# Layout_Design_File.net
KiCad netlist of a schematic drawn in EAGLE
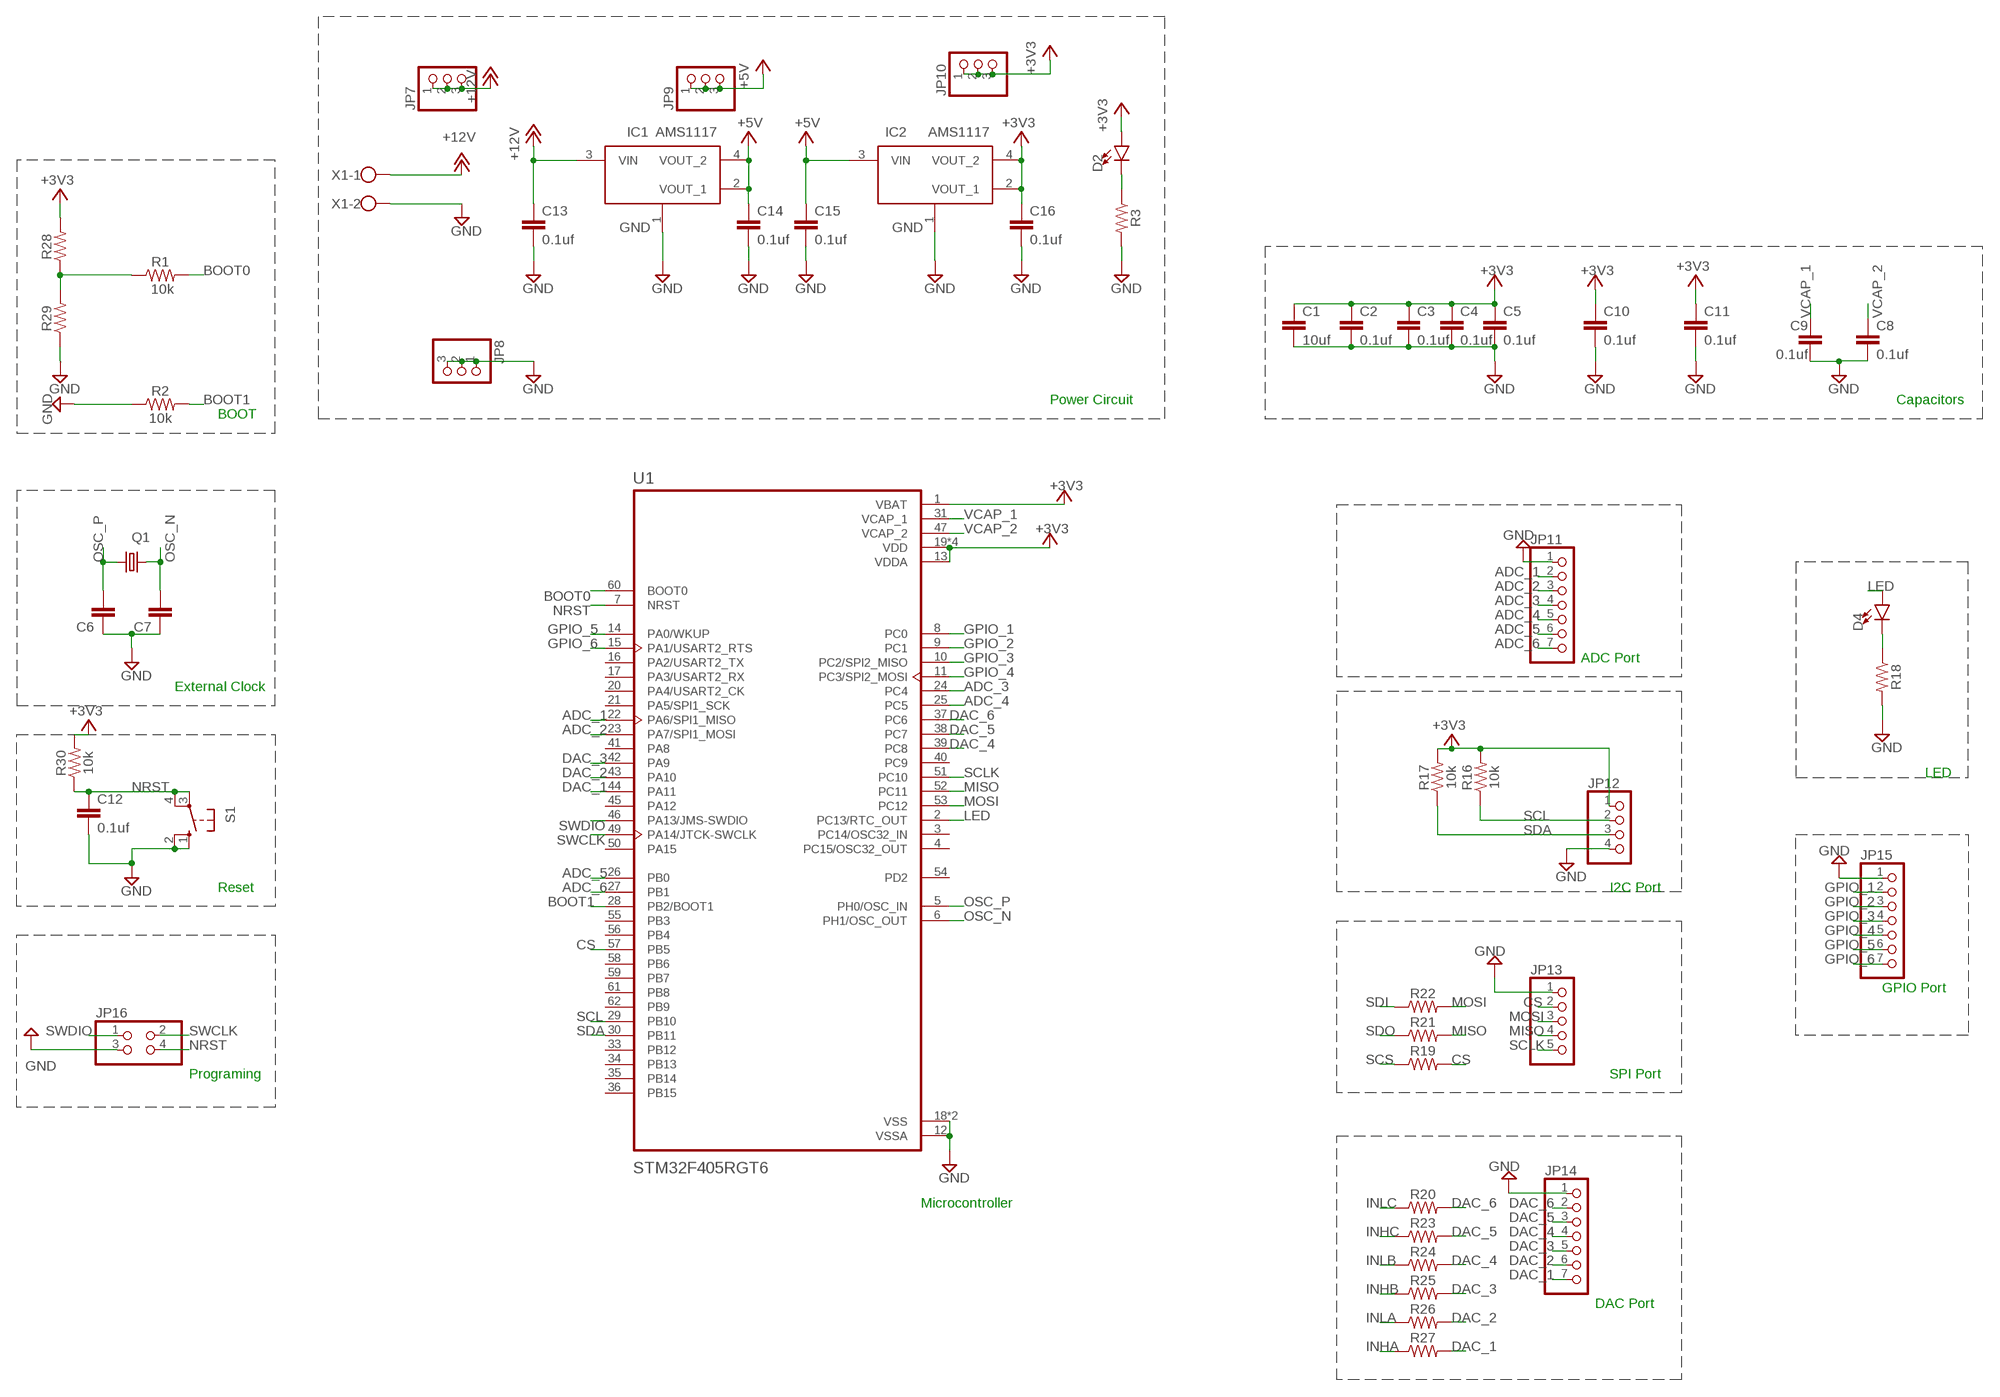
[diagram p0: schematic, sheet 1]
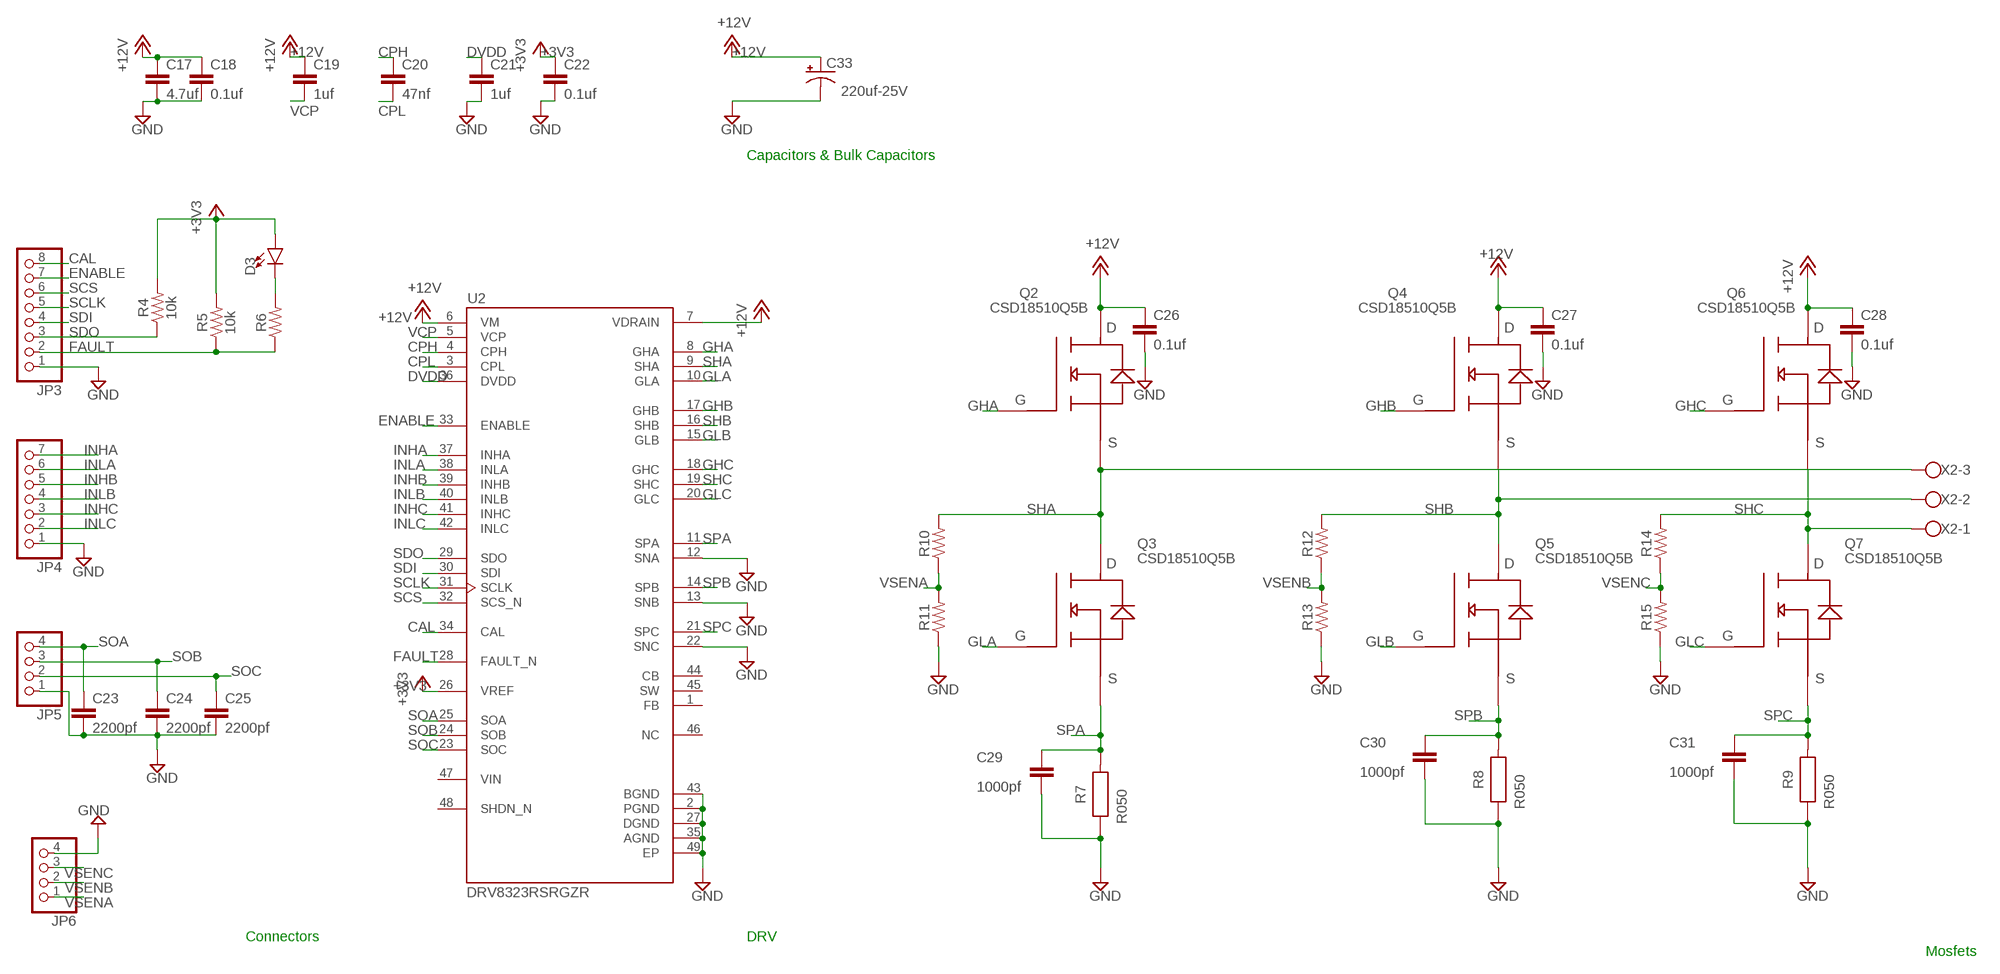
[diagram p1: schematic, sheet 2]

(export (version "E")
  (design (tool "Eeschema 10.0.6"))
  (components
    (comp (ref "C1")
      (value "10uf")
      (footprint "eagle-import:0603")
      (libsource (lib "eagle-import") (part "CAP-0603"))
    )
    (comp (ref "C2")
      (value "0.1uf")
      (footprint "eagle-import:0603")
      (libsource (lib "eagle-import") (part "CAP-0603"))
    )
    (comp (ref "C3")
      (value "0.1uf")
      (footprint "eagle-import:0603")
      (libsource (lib "eagle-import") (part "CAP-0603"))
    )
    (comp (ref "C4")
      (value "0.1uf")
      (footprint "eagle-import:0603")
      (libsource (lib "eagle-import") (part "CAP-0603"))
    )
    (comp (ref "C5")
      (value "0.1uf")
      (footprint "eagle-import:0603")
      (libsource (lib "eagle-import") (part "CAP-0603"))
    )
    (comp (ref "C6")
      (value "CAP-0603")
      (footprint "eagle-import:0603")
      (libsource (lib "eagle-import") (part "CAP-0603"))
    )
    (comp (ref "C7")
      (value "CAP-0603")
      (footprint "eagle-import:0603")
      (libsource (lib "eagle-import") (part "CAP-0603"))
    )
    (comp (ref "C8")
      (value "0.1uf")
      (footprint "eagle-import:0603")
      (libsource (lib "eagle-import") (part "CAP-0603"))
    )
    (comp (ref "C9")
      (value "0.1uf")
      (footprint "eagle-import:0603")
      (libsource (lib "eagle-import") (part "CAP-0603"))
    )
    (comp (ref "C10")
      (value "0.1uf")
      (footprint "eagle-import:0603")
      (libsource (lib "eagle-import") (part "CAP-0603"))
    )
    (comp (ref "C11")
      (value "0.1uf")
      (footprint "eagle-import:0603")
      (libsource (lib "eagle-import") (part "CAP-0603"))
    )
    (comp (ref "C12")
      (value "0.1uf")
      (footprint "eagle-import:0603")
      (libsource (lib "eagle-import") (part "CAP-0603"))
    )
    (comp (ref "C13")
      (value "0.1uf")
      (footprint "eagle-import:0603")
      (libsource (lib "eagle-import") (part "CAP-0603"))
    )
    (comp (ref "C14")
      (value "0.1uf")
      (footprint "eagle-import:0603")
      (libsource (lib "eagle-import") (part "CAP-0603"))
    )
    (comp (ref "C15")
      (value "0.1uf")
      (footprint "eagle-import:0603")
      (libsource (lib "eagle-import") (part "CAP-0603"))
    )
    (comp (ref "C16")
      (value "0.1uf")
      (footprint "eagle-import:0603")
      (libsource (lib "eagle-import") (part "CAP-0603"))
    )
    (comp (ref "D2")
      (value "LED1206")
      (footprint "eagle-import:LED-1206")
      (libsource (lib "eagle-import") (part "LED1206"))
    )
    (comp (ref "D4")
      (value "LED1206")
      (footprint "eagle-import:LED-1206")
      (libsource (lib "eagle-import") (part "LED1206"))
    )
    (comp (ref "IC1")
      (value "AMS1117")
      (footprint "eagle-import:SOT229P700X180-4N")
      (libsource (lib "eagle-import") (part "AMS1117"))
    )
    (comp (ref "IC2")
      (value "AMS1117")
      (footprint "eagle-import:SOT229P700X180-4N")
      (libsource (lib "eagle-import") (part "AMS1117"))
    )
    (comp (ref "JP7")
      (value "PINHD-1X3")
      (footprint "eagle-import:1X03")
      (libsource (lib "eagle-import") (part "PINHD-1X3"))
    )
    (comp (ref "JP8")
      (value "PINHD-1X3")
      (footprint "eagle-import:1X03")
      (libsource (lib "eagle-import") (part "PINHD-1X3"))
    )
    (comp (ref "JP9")
      (value "PINHD-1X3")
      (footprint "eagle-import:1X03")
      (libsource (lib "eagle-import") (part "PINHD-1X3"))
    )
    (comp (ref "JP10")
      (value "PINHD-1X3")
      (footprint "eagle-import:1X03")
      (libsource (lib "eagle-import") (part "PINHD-1X3"))
    )
    (comp (ref "JP11")
      (value "PINHD-1X7")
      (footprint "eagle-import:1X07")
      (libsource (lib "eagle-import") (part "PINHD-1X7"))
    )
    (comp (ref "JP12")
      (value "PINHD-1X4")
      (footprint "eagle-import:1X04")
      (libsource (lib "eagle-import") (part "PINHD-1X4"))
    )
    (comp (ref "JP13")
      (value "PINHD-1X5")
      (footprint "eagle-import:1X05")
      (libsource (lib "eagle-import") (part "PINHD-1X5"))
    )
    (comp (ref "JP14")
      (value "PINHD-1X7")
      (footprint "eagle-import:1X07")
      (libsource (lib "eagle-import") (part "PINHD-1X7"))
    )
    (comp (ref "JP15")
      (value "PINHD-1X7")
      (footprint "eagle-import:1X07")
      (libsource (lib "eagle-import") (part "PINHD-1X7"))
    )
    (comp (ref "JP16")
      (value "PINHD-2X2")
      (footprint "eagle-import:2X02")
      (libsource (lib "eagle-import") (part "PINHD-2X2"))
    )
    (comp (ref "Q1")
      (value "CRYSTALHC49S")
      (footprint "eagle-import:HC49_S")
      (libsource (lib "eagle-import") (part "CRYSTALHC49S"))
    )
    (comp (ref "R1")
      (value "10k")
      (footprint "eagle-import:0603")
      (libsource (lib "eagle-import") (part "RESISTOR0603"))
    )
    (comp (ref "R2")
      (value "10k")
      (footprint "eagle-import:0603")
      (libsource (lib "eagle-import") (part "RESISTOR0603"))
    )
    (comp (ref "R3")
      (value "RESISTOR0603")
      (footprint "eagle-import:0603")
      (libsource (lib "eagle-import") (part "RESISTOR0603"))
    )
    (comp (ref "R16")
      (value "10k")
      (footprint "eagle-import:0603")
      (libsource (lib "eagle-import") (part "RESISTOR0603"))
    )
    (comp (ref "R17")
      (value "10k")
      (footprint "eagle-import:0603")
      (libsource (lib "eagle-import") (part "RESISTOR0603"))
    )
    (comp (ref "R18")
      (value "RESISTOR0603")
      (footprint "eagle-import:0603")
      (libsource (lib "eagle-import") (part "RESISTOR0603"))
    )
    (comp (ref "R19")
      (value "RESISTOR0603")
      (footprint "eagle-import:0603")
      (libsource (lib "eagle-import") (part "RESISTOR0603"))
    )
    (comp (ref "R20")
      (value "RESISTOR0603")
      (footprint "eagle-import:0603")
      (libsource (lib "eagle-import") (part "RESISTOR0603"))
    )
    (comp (ref "R21")
      (value "RESISTOR0603")
      (footprint "eagle-import:0603")
      (libsource (lib "eagle-import") (part "RESISTOR0603"))
    )
    (comp (ref "R22")
      (value "RESISTOR0603")
      (footprint "eagle-import:0603")
      (libsource (lib "eagle-import") (part "RESISTOR0603"))
    )
    (comp (ref "R23")
      (value "RESISTOR0603")
      (footprint "eagle-import:0603")
      (libsource (lib "eagle-import") (part "RESISTOR0603"))
    )
    (comp (ref "R24")
      (value "RESISTOR0603")
      (footprint "eagle-import:0603")
      (libsource (lib "eagle-import") (part "RESISTOR0603"))
    )
    (comp (ref "R25")
      (value "RESISTOR0603")
      (footprint "eagle-import:0603")
      (libsource (lib "eagle-import") (part "RESISTOR0603"))
    )
    (comp (ref "R26")
      (value "RESISTOR0603")
      (footprint "eagle-import:0603")
      (libsource (lib "eagle-import") (part "RESISTOR0603"))
    )
    (comp (ref "R27")
      (value "RESISTOR0603")
      (footprint "eagle-import:0603")
      (libsource (lib "eagle-import") (part "RESISTOR0603"))
    )
    (comp (ref "R28")
      (value "RESISTOR0603")
      (footprint "eagle-import:0603")
      (libsource (lib "eagle-import") (part "RESISTOR0603"))
    )
    (comp (ref "R29")
      (value "RESISTOR0603")
      (footprint "eagle-import:0603")
      (libsource (lib "eagle-import") (part "RESISTOR0603"))
    )
    (comp (ref "R30")
      (value "10k")
      (footprint "eagle-import:0603")
      (libsource (lib "eagle-import") (part "RESISTOR0603"))
    )
    (comp (ref "S1")
      (value "10-XX")
      (footprint "eagle-import:B3F-10XX")
      (fields (field (name "MPN") "B3F-1000"))
      (libsource (lib "eagle-import") (part "10-XX"))
    )
    (comp (ref "U1")
      (value "STM32F405RGT6")
      (footprint "eagle-import:QFP50P1200X1200X160-64N")
      (fields (field (name "MF") "STMicroelectronics"))
      (libsource (lib "eagle-import") (part "STM32F405RGT6"))
    )
    (comp (ref "X1")
      (value "W237-102")
      (footprint "eagle-import:W237-102")
      (fields (field (name "MPN") "237-102"))
      (libsource (lib "eagle-import") (part "W237-102"))
    )
    (comp (ref "C17")
      (value "4.7uf")
      (footprint "eagle-import:0603")
      (libsource (lib "eagle-import") (part "CAP-0603"))
    )
    (comp (ref "C18")
      (value "0.1uf")
      (footprint "eagle-import:0603")
      (libsource (lib "eagle-import") (part "CAP-0603"))
    )
    (comp (ref "C19")
      (value "1uf")
      (footprint "eagle-import:0603")
      (libsource (lib "eagle-import") (part "CAP-0603"))
    )
    (comp (ref "C20")
      (value "47nf")
      (footprint "eagle-import:0603")
      (libsource (lib "eagle-import") (part "CAP-0603"))
    )
    (comp (ref "C21")
      (value "1uf")
      (footprint "eagle-import:0603")
      (libsource (lib "eagle-import") (part "CAP-0603"))
    )
    (comp (ref "C22")
      (value "0.1uf")
      (footprint "eagle-import:0603")
      (libsource (lib "eagle-import") (part "CAP-0603"))
    )
    (comp (ref "C23")
      (value "2200pf")
      (footprint "eagle-import:0603")
      (libsource (lib "eagle-import") (part "CAP-0603"))
    )
    (comp (ref "C24")
      (value "2200pf")
      (footprint "eagle-import:0603")
      (libsource (lib "eagle-import") (part "CAP-0603"))
    )
    (comp (ref "C25")
      (value "2200pf")
      (footprint "eagle-import:0603")
      (libsource (lib "eagle-import") (part "CAP-0603"))
    )
    (comp (ref "C26")
      (value "0.1uf")
      (footprint "eagle-import:0603")
      (libsource (lib "eagle-import") (part "CAP-0603"))
    )
    (comp (ref "C27")
      (value "0.1uf")
      (footprint "eagle-import:0603")
      (libsource (lib "eagle-import") (part "CAP-0603"))
    )
    (comp (ref "C28")
      (value "0.1uf")
      (footprint "eagle-import:0603")
      (libsource (lib "eagle-import") (part "CAP-0603"))
    )
    (comp (ref "C29")
      (value "1000pf")
      (footprint "eagle-import:0603")
      (libsource (lib "eagle-import") (part "CAP-0603"))
    )
    (comp (ref "C30")
      (value "1000pf")
      (footprint "eagle-import:0603")
      (libsource (lib "eagle-import") (part "CAP-0603"))
    )
    (comp (ref "C31")
      (value "1000pf")
      (footprint "eagle-import:0603")
      (libsource (lib "eagle-import") (part "CAP-0603"))
    )
    (comp (ref "C33")
      (value "220uf-25V")
      (footprint "eagle-import:CPOL-RADIAL-5MM-10MM-NS")
      (libsource (lib "eagle-import") (part "1000UF-RADIAL-5MM-25V-20%-NO-SILK"))
    )
    (comp (ref "D3")
      (value "LED1206")
      (footprint "eagle-import:LED-1206")
      (libsource (lib "eagle-import") (part "LED1206"))
    )
    (comp (ref "JP3")
      (value "PINHD-1X8")
      (footprint "eagle-import:1X08")
      (libsource (lib "eagle-import") (part "PINHD-1X8"))
    )
    (comp (ref "JP4")
      (value "PINHD-1X7")
      (footprint "eagle-import:1X07")
      (libsource (lib "eagle-import") (part "PINHD-1X7"))
    )
    (comp (ref "JP5")
      (value "PINHD-1X4")
      (footprint "eagle-import:1X04")
      (libsource (lib "eagle-import") (part "PINHD-1X4"))
    )
    (comp (ref "JP6")
      (value "PINHD-1X4")
      (footprint "eagle-import:1X04")
      (libsource (lib "eagle-import") (part "PINHD-1X4"))
    )
    (comp (ref "Q2")
      (value "CSD18510Q5B")
      (footprint "eagle-import:CSD18540Q5BT")
      (fields (field (name "MOUSER_PART_NUMBER") "595-CSD18510Q5B"))
      (libsource (lib "eagle-import") (part "CSD18510Q5B"))
    )
    (comp (ref "Q3")
      (value "CSD18510Q5B")
      (footprint "eagle-import:CSD18540Q5BT")
      (fields (field (name "MOUSER_PART_NUMBER") "595-CSD18510Q5B"))
      (libsource (lib "eagle-import") (part "CSD18510Q5B"))
    )
    (comp (ref "Q4")
      (value "CSD18510Q5B")
      (footprint "eagle-import:CSD18540Q5BT")
      (fields (field (name "MOUSER_PART_NUMBER") "595-CSD18510Q5B"))
      (libsource (lib "eagle-import") (part "CSD18510Q5B"))
    )
    (comp (ref "Q5")
      (value "CSD18510Q5B")
      (footprint "eagle-import:CSD18540Q5BT")
      (fields (field (name "MOUSER_PART_NUMBER") "595-CSD18510Q5B"))
      (libsource (lib "eagle-import") (part "CSD18510Q5B"))
    )
    (comp (ref "Q6")
      (value "CSD18510Q5B")
      (footprint "eagle-import:CSD18540Q5BT")
      (fields (field (name "MOUSER_PART_NUMBER") "595-CSD18510Q5B"))
      (libsource (lib "eagle-import") (part "CSD18510Q5B"))
    )
    (comp (ref "Q7")
      (value "CSD18510Q5B")
      (footprint "eagle-import:CSD18540Q5BT")
      (fields (field (name "MOUSER_PART_NUMBER") "595-CSD18510Q5B"))
      (libsource (lib "eagle-import") (part "CSD18510Q5B"))
    )
    (comp (ref "R4")
      (value "10k")
      (footprint "eagle-import:0603")
      (libsource (lib "eagle-import") (part "RESISTOR0603"))
    )
    (comp (ref "R5")
      (value "10k")
      (footprint "eagle-import:0603")
      (libsource (lib "eagle-import") (part "RESISTOR0603"))
    )
    (comp (ref "R6")
      (value "RESISTOR0603")
      (footprint "eagle-import:0603")
      (libsource (lib "eagle-import") (part "RESISTOR0603"))
    )
    (comp (ref "R7")
      (value "R050")
      (footprint "eagle-import:WRIS_PSMC_2512_6.3X3.1X0.58X2.2(LXWXHXPW)")
      (libsource (lib "eagle-import") (part "WRIS-PSMC_2512_6.3X3.1X0.58X2.2_580070763001"))
    )
    (comp (ref "R8")
      (value "R050")
      (footprint "eagle-import:WRIS_PSMC_2512_6.3X3.1X0.58X2.2(LXWXHXPW)")
      (libsource (lib "eagle-import") (part "WRIS-PSMC_2512_6.3X3.1X0.58X2.2_580070763001"))
    )
    (comp (ref "R9")
      (value "R050")
      (footprint "eagle-import:WRIS_PSMC_2512_6.3X3.1X0.58X2.2(LXWXHXPW)")
      (libsource (lib "eagle-import") (part "WRIS-PSMC_2512_6.3X3.1X0.58X2.2_580070763001"))
    )
    (comp (ref "R10")
      (value "RESISTOR0603")
      (footprint "eagle-import:0603")
      (libsource (lib "eagle-import") (part "RESISTOR0603"))
    )
    (comp (ref "R11")
      (value "RESISTOR0603")
      (footprint "eagle-import:0603")
      (libsource (lib "eagle-import") (part "RESISTOR0603"))
    )
    (comp (ref "R12")
      (value "RESISTOR0603")
      (footprint "eagle-import:0603")
      (libsource (lib "eagle-import") (part "RESISTOR0603"))
    )
    (comp (ref "R13")
      (value "RESISTOR0603")
      (footprint "eagle-import:0603")
      (libsource (lib "eagle-import") (part "RESISTOR0603"))
    )
    (comp (ref "R14")
      (value "RESISTOR0603")
      (footprint "eagle-import:0603")
      (libsource (lib "eagle-import") (part "RESISTOR0603"))
    )
    (comp (ref "R15")
      (value "RESISTOR0603")
      (footprint "eagle-import:0603")
      (libsource (lib "eagle-import") (part "RESISTOR0603"))
    )
    (comp (ref "U2")
      (value "DRV8323RSRGZR")
      (footprint "eagle-import:QFN50P700X700X100-49N")
      (fields (field (name "MF") "Texas Instruments"))
      (libsource (lib "eagle-import") (part "DRV8323RSRGZR"))
    )
    (comp (ref "X2")
      (value "W237-103")
      (footprint "eagle-import:W237-103")
      (fields (field (name "MPN") "237-103"))
      (libsource (lib "eagle-import") (part "W237-103"))
    )
  )
  (nets
    (net (code "1") (name "+3V3") (class "Default")
      (node (ref "C1") (pin "1") (pinfunction "1_1") (pintype "passive"))
      (node (ref "C10") (pin "1") (pinfunction "1_1") (pintype "passive"))
      (node (ref "C11") (pin "1") (pinfunction "1_1") (pintype "passive"))
      (node (ref "C16") (pin "1") (pinfunction "1_1") (pintype "passive"))
      (node (ref "C2") (pin "1") (pinfunction "1_1") (pintype "passive"))
      (node (ref "C22") (pin "1") (pinfunction "1_1") (pintype "passive"))
      (node (ref "C3") (pin "1") (pinfunction "1_1") (pintype "passive"))
      (node (ref "C4") (pin "1") (pinfunction "1_1") (pintype "passive"))
      (node (ref "C5") (pin "1") (pinfunction "1_1") (pintype "passive"))
      (node (ref "D2") (pin "A") (pinfunction "A_A") (pintype "passive"))
      (node (ref "D3") (pin "A") (pinfunction "A_A") (pintype "passive"))
      (node (ref "IC2") (pin "2") (pinfunction "VOUT_1_2") (pintype "bidirectional"))
      (node (ref "IC2") (pin "4") (pinfunction "VOUT_2_4") (pintype "bidirectional"))
      (node (ref "JP10") (pin "1") (pinfunction "1_1") (pintype "passive"))
      (node (ref "JP10") (pin "2") (pinfunction "2_2") (pintype "passive"))
      (node (ref "JP10") (pin "3") (pinfunction "3_3") (pintype "passive"))
      (node (ref "JP12") (pin "1") (pinfunction "1_1") (pintype "passive"))
      (node (ref "R16") (pin "2") (pinfunction "2_2") (pintype "passive"))
      (node (ref "R17") (pin "2") (pinfunction "2_2") (pintype "passive"))
      (node (ref "R28") (pin "2") (pinfunction "2_2") (pintype "passive"))
      (node (ref "R30") (pin "2") (pinfunction "2_2") (pintype "passive"))
      (node (ref "R4") (pin "2") (pinfunction "2_2") (pintype "passive"))
      (node (ref "R5") (pin "2") (pinfunction "2_2") (pintype "passive"))
      (node (ref "U1") (pin "1") (pinfunction "VBAT_1") (pintype "power_in"))
      (node (ref "U1") (pin "13") (pinfunction "VDDA_13") (pintype "power_in"))
      (node (ref "U1") (pin "19") (pinfunction "VDD_19") (pintype "power_in"))
      (node (ref "U1") (pin "32") (pinfunction "VDD_32") (pintype "power_in"))
      (node (ref "U1") (pin "48") (pinfunction "VDD_48") (pintype "power_in"))
      (node (ref "U1") (pin "64") (pinfunction "VDD_64") (pintype "power_in"))
      (node (ref "U2") (pin "26") (pinfunction "VREF_26") (pintype "power_in"))
    )
    (net (code "2") (name "+5V") (class "Default")
      (node (ref "C14") (pin "1") (pinfunction "1_1") (pintype "passive"))
      (node (ref "C15") (pin "1") (pinfunction "1_1") (pintype "passive"))
      (node (ref "IC1") (pin "2") (pinfunction "VOUT_1_2") (pintype "bidirectional"))
      (node (ref "IC1") (pin "4") (pinfunction "VOUT_2_4") (pintype "bidirectional"))
      (node (ref "IC2") (pin "3") (pinfunction "VIN_3") (pintype "bidirectional"))
      (node (ref "JP9") (pin "1") (pinfunction "1_1") (pintype "passive"))
      (node (ref "JP9") (pin "2") (pinfunction "2_2") (pintype "passive"))
      (node (ref "JP9") (pin "3") (pinfunction "3_3") (pintype "passive"))
    )
    (net (code "3") (name "+12V") (class "Default")
      (node (ref "C13") (pin "1") (pinfunction "1_1") (pintype "passive"))
      (node (ref "C17") (pin "1") (pinfunction "1_1") (pintype "passive"))
      (node (ref "C18") (pin "1") (pinfunction "1_1") (pintype "passive"))
      (node (ref "C19") (pin "1") (pinfunction "1_1") (pintype "passive"))
      (node (ref "C26") (pin "1") (pinfunction "1_1") (pintype "passive"))
      (node (ref "C27") (pin "1") (pinfunction "1_1") (pintype "passive"))
      (node (ref "C28") (pin "1") (pinfunction "1_1") (pintype "passive"))
      (node (ref "C33") (pin "+") (pinfunction "+_+") (pintype "passive"))
      (node (ref "IC1") (pin "3") (pinfunction "VIN_3") (pintype "bidirectional"))
      (node (ref "JP7") (pin "1") (pinfunction "1_1") (pintype "passive"))
      (node (ref "JP7") (pin "2") (pinfunction "2_2") (pintype "passive"))
      (node (ref "JP7") (pin "3") (pinfunction "3_3") (pintype "passive"))
      (node (ref "Q2") (pin "5") (pinfunction "D_5") (pintype "bidirectional"))
      (node (ref "Q2") (pin "6") (pinfunction "D_6") (pintype "bidirectional"))
      (node (ref "Q2") (pin "7") (pinfunction "D_7") (pintype "bidirectional"))
      (node (ref "Q2") (pin "8") (pinfunction "D_8") (pintype "bidirectional"))
      (node (ref "Q2") (pin "9") (pinfunction "D_9") (pintype "bidirectional"))
      (node (ref "Q4") (pin "5") (pinfunction "D_5") (pintype "bidirectional"))
      (node (ref "Q4") (pin "6") (pinfunction "D_6") (pintype "bidirectional"))
      (node (ref "Q4") (pin "7") (pinfunction "D_7") (pintype "bidirectional"))
      (node (ref "Q4") (pin "8") (pinfunction "D_8") (pintype "bidirectional"))
      (node (ref "Q4") (pin "9") (pinfunction "D_9") (pintype "bidirectional"))
      (node (ref "Q6") (pin "5") (pinfunction "D_5") (pintype "bidirectional"))
      (node (ref "Q6") (pin "6") (pinfunction "D_6") (pintype "bidirectional"))
      (node (ref "Q6") (pin "7") (pinfunction "D_7") (pintype "bidirectional"))
      (node (ref "Q6") (pin "8") (pinfunction "D_8") (pintype "bidirectional"))
      (node (ref "Q6") (pin "9") (pinfunction "D_9") (pintype "bidirectional"))
      (node (ref "U2") (pin "6") (pinfunction "VM_6") (pintype "power_in"))
      (node (ref "U2") (pin "7") (pinfunction "VDRAIN_7") (pintype "input"))
      (node (ref "X1") (pin "1") (pinfunction "KL_1") (pintype "passive"))
    )
    (net (code "4") (name "ADC_1") (class "Default")
      (node (ref "JP11") (pin "2") (pinfunction "2_2") (pintype "passive"))
      (node (ref "U1") (pin "22") (pinfunction "PA6/SPI1_MISO_22") (pintype "bidirectional"))
    )
    (net (code "5") (name "ADC_2") (class "Default")
      (node (ref "JP11") (pin "3") (pinfunction "3_3") (pintype "passive"))
      (node (ref "U1") (pin "23") (pinfunction "PA7/SPI1_MOSI_23") (pintype "bidirectional"))
    )
    (net (code "6") (name "ADC_3") (class "Default")
      (node (ref "JP11") (pin "4") (pinfunction "4_4") (pintype "passive"))
      (node (ref "U1") (pin "24") (pinfunction "PC4_24") (pintype "bidirectional"))
    )
    (net (code "7") (name "ADC_4") (class "Default")
      (node (ref "JP11") (pin "5") (pinfunction "5_5") (pintype "passive"))
      (node (ref "U1") (pin "25") (pinfunction "PC5_25") (pintype "bidirectional"))
    )
    (net (code "8") (name "ADC_5") (class "Default")
      (node (ref "JP11") (pin "6") (pinfunction "6_6") (pintype "passive"))
      (node (ref "U1") (pin "26") (pinfunction "PB0_26") (pintype "bidirectional"))
    )
    (net (code "9") (name "ADC_6") (class "Default")
      (node (ref "JP11") (pin "7") (pinfunction "7_7") (pintype "passive"))
      (node (ref "U1") (pin "27") (pinfunction "PB1_27") (pintype "bidirectional"))
    )
    (net (code "10") (name "BOOT0") (class "Default")
      (node (ref "R1") (pin "2") (pinfunction "2_2") (pintype "passive"))
      (node (ref "U1") (pin "60") (pinfunction "BOOT0_60") (pintype "bidirectional"))
    )
    (net (code "11") (name "BOOT1") (class "Default")
      (node (ref "R2") (pin "2") (pinfunction "2_2") (pintype "passive"))
      (node (ref "U1") (pin "28") (pinfunction "PB2/BOOT1_28") (pintype "bidirectional"))
    )
    (net (code "12") (name "CAL") (class "Default")
      (node (ref "JP3") (pin "8") (pinfunction "8_8") (pintype "passive"))
      (node (ref "U2") (pin "34") (pinfunction "CAL_34") (pintype "input"))
    )
    (net (code "13") (name "CB") (class "Default")
      (node (ref "U2") (pin "44") (pinfunction "CB_44") (pintype "power_in"))
    )
    (net (code "14") (name "CPH") (class "Default")
      (node (ref "C20") (pin "1") (pinfunction "1_1") (pintype "passive"))
      (node (ref "U2") (pin "4") (pinfunction "CPH_4") (pintype "passive"))
    )
    (net (code "15") (name "CPL") (class "Default")
      (node (ref "C20") (pin "2") (pinfunction "2_2") (pintype "passive"))
      (node (ref "U2") (pin "3") (pinfunction "CPL_3") (pintype "passive"))
    )
    (net (code "16") (name "CS") (class "Default")
      (node (ref "JP13") (pin "2") (pinfunction "2_2") (pintype "passive"))
      (node (ref "R19") (pin "2") (pinfunction "2_2") (pintype "passive"))
      (node (ref "U1") (pin "57") (pinfunction "PB5_57") (pintype "bidirectional"))
    )
    (net (code "17") (name "DAC_1") (class "Default")
      (node (ref "JP14") (pin "7") (pinfunction "7_7") (pintype "passive"))
      (node (ref "R27") (pin "2") (pinfunction "2_2") (pintype "passive"))
      (node (ref "U1") (pin "44") (pinfunction "PA11_44") (pintype "bidirectional"))
    )
    (net (code "18") (name "DAC_2") (class "Default")
      (node (ref "JP14") (pin "6") (pinfunction "6_6") (pintype "passive"))
      (node (ref "R26") (pin "2") (pinfunction "2_2") (pintype "passive"))
      (node (ref "U1") (pin "43") (pinfunction "PA10_43") (pintype "bidirectional"))
    )
    (net (code "19") (name "DAC_3") (class "Default")
      (node (ref "JP14") (pin "5") (pinfunction "5_5") (pintype "passive"))
      (node (ref "R25") (pin "2") (pinfunction "2_2") (pintype "passive"))
      (node (ref "U1") (pin "42") (pinfunction "PA9_42") (pintype "bidirectional"))
    )
    (net (code "20") (name "DAC_4") (class "Default")
      (node (ref "JP14") (pin "4") (pinfunction "4_4") (pintype "passive"))
      (node (ref "R24") (pin "2") (pinfunction "2_2") (pintype "passive"))
      (node (ref "U1") (pin "39") (pinfunction "PC8_39") (pintype "bidirectional"))
    )
    (net (code "21") (name "DAC_5") (class "Default")
      (node (ref "JP14") (pin "3") (pinfunction "3_3") (pintype "passive"))
      (node (ref "R23") (pin "2") (pinfunction "2_2") (pintype "passive"))
      (node (ref "U1") (pin "38") (pinfunction "PC7_38") (pintype "bidirectional"))
    )
    (net (code "22") (name "DAC_6") (class "Default")
      (node (ref "JP14") (pin "2") (pinfunction "2_2") (pintype "passive"))
      (node (ref "R20") (pin "2") (pinfunction "2_2") (pintype "passive"))
      (node (ref "U1") (pin "37") (pinfunction "PC6_37") (pintype "bidirectional"))
    )
    (net (code "23") (name "DVDD") (class "Default")
      (node (ref "C21") (pin "1") (pinfunction "1_1") (pintype "passive"))
      (node (ref "U2") (pin "36") (pinfunction "DVDD_36") (pintype "power_in"))
    )
    (net (code "24") (name "ENABLE") (class "Default")
      (node (ref "JP3") (pin "7") (pinfunction "7_7") (pintype "passive"))
      (node (ref "U2") (pin "33") (pinfunction "ENABLE_33") (pintype "input"))
    )
    (net (code "25") (name "FAULT") (class "Default")
      (node (ref "JP3") (pin "2") (pinfunction "2_2") (pintype "passive"))
      (node (ref "R5") (pin "1") (pinfunction "1_1") (pintype "passive"))
      (node (ref "R6") (pin "1") (pinfunction "1_1") (pintype "passive"))
      (node (ref "U2") (pin "28") (pinfunction "FAULT_N_28") (pintype "output"))
    )
    (net (code "26") (name "GHA") (class "Default")
      (node (ref "Q2") (pin "4") (pinfunction "G_4") (pintype "bidirectional"))
      (node (ref "U2") (pin "8") (pinfunction "GHA_8") (pintype "output"))
    )
    (net (code "27") (name "GHB") (class "Default")
      (node (ref "Q4") (pin "4") (pinfunction "G_4") (pintype "bidirectional"))
      (node (ref "U2") (pin "17") (pinfunction "GHB_17") (pintype "output"))
    )
    (net (code "28") (name "GHC") (class "Default")
      (node (ref "Q6") (pin "4") (pinfunction "G_4") (pintype "bidirectional"))
      (node (ref "U2") (pin "18") (pinfunction "GHC_18") (pintype "output"))
    )
    (net (code "29") (name "GLA") (class "Default")
      (node (ref "Q3") (pin "4") (pinfunction "G_4") (pintype "bidirectional"))
      (node (ref "U2") (pin "10") (pinfunction "GLA_10") (pintype "output"))
    )
    (net (code "30") (name "GLB") (class "Default")
      (node (ref "Q5") (pin "4") (pinfunction "G_4") (pintype "bidirectional"))
      (node (ref "U2") (pin "15") (pinfunction "GLB_15") (pintype "output"))
    )
    (net (code "31") (name "GLC") (class "Default")
      (node (ref "Q7") (pin "4") (pinfunction "G_4") (pintype "bidirectional"))
      (node (ref "U2") (pin "20") (pinfunction "GLC_20") (pintype "output"))
    )
    (net (code "32") (name "GND") (class "Default")
      (node (ref "C1") (pin "2") (pinfunction "2_2") (pintype "passive"))
      (node (ref "C10") (pin "2") (pinfunction "2_2") (pintype "passive"))
      (node (ref "C11") (pin "2") (pinfunction "2_2") (pintype "passive"))
      (node (ref "C12") (pin "2") (pinfunction "2_2") (pintype "passive"))
      (node (ref "C13") (pin "2") (pinfunction "2_2") (pintype "passive"))
      (node (ref "C14") (pin "2") (pinfunction "2_2") (pintype "passive"))
      (node (ref "C15") (pin "2") (pinfunction "2_2") (pintype "passive"))
      (node (ref "C16") (pin "2") (pinfunction "2_2") (pintype "passive"))
      (node (ref "C17") (pin "2") (pinfunction "2_2") (pintype "passive"))
      (node (ref "C18") (pin "2") (pinfunction "2_2") (pintype "passive"))
      (node (ref "C2") (pin "2") (pinfunction "2_2") (pintype "passive"))
      (node (ref "C21") (pin "2") (pinfunction "2_2") (pintype "passive"))
      (node (ref "C22") (pin "2") (pinfunction "2_2") (pintype "passive"))
      (node (ref "C23") (pin "2") (pinfunction "2_2") (pintype "passive"))
      (node (ref "C24") (pin "2") (pinfunction "2_2") (pintype "passive"))
      (node (ref "C25") (pin "2") (pinfunction "2_2") (pintype "passive"))
      (node (ref "C26") (pin "2") (pinfunction "2_2") (pintype "passive"))
      (node (ref "C27") (pin "2") (pinfunction "2_2") (pintype "passive"))
      (node (ref "C28") (pin "2") (pinfunction "2_2") (pintype "passive"))
      (node (ref "C29") (pin "2") (pinfunction "2_2") (pintype "passive"))
      (node (ref "C3") (pin "2") (pinfunction "2_2") (pintype "passive"))
      (node (ref "C30") (pin "2") (pinfunction "2_2") (pintype "passive"))
      (node (ref "C31") (pin "2") (pinfunction "2_2") (pintype "passive"))
      (node (ref "C33") (pin "-") (pinfunction "-_-") (pintype "passive"))
      (node (ref "C4") (pin "2") (pinfunction "2_2") (pintype "passive"))
      (node (ref "C5") (pin "2") (pinfunction "2_2") (pintype "passive"))
      (node (ref "C6") (pin "1") (pinfunction "1_1") (pintype "passive"))
      (node (ref "C7") (pin "1") (pinfunction "1_1") (pintype "passive"))
      (node (ref "C8") (pin "2") (pinfunction "2_2") (pintype "passive"))
      (node (ref "C9") (pin "2") (pinfunction "2_2") (pintype "passive"))
      (node (ref "IC1") (pin "1") (pinfunction "GND_1") (pintype "bidirectional"))
      (node (ref "IC2") (pin "1") (pinfunction "GND_1") (pintype "bidirectional"))
      (node (ref "JP11") (pin "1") (pinfunction "1_1") (pintype "passive"))
      (node (ref "JP12") (pin "4") (pinfunction "4_4") (pintype "passive"))
      (node (ref "JP13") (pin "1") (pinfunction "1_1") (pintype "passive"))
      (node (ref "JP14") (pin "1") (pinfunction "1_1") (pintype "passive"))
      (node (ref "JP15") (pin "1") (pinfunction "1_1") (pintype "passive"))
      (node (ref "JP16") (pin "3") (pinfunction "3_3") (pintype "passive"))
      (node (ref "JP3") (pin "1") (pinfunction "1_1") (pintype "passive"))
      (node (ref "JP4") (pin "1") (pinfunction "1_1") (pintype "passive"))
      (node (ref "JP5") (pin "1") (pinfunction "1_1") (pintype "passive"))
      (node (ref "JP6") (pin "4") (pinfunction "4_4") (pintype "passive"))
      (node (ref "JP8") (pin "1") (pinfunction "1_1") (pintype "passive"))
      (node (ref "JP8") (pin "2") (pinfunction "2_2") (pintype "passive"))
      (node (ref "JP8") (pin "3") (pinfunction "3_3") (pintype "passive"))
      (node (ref "R11") (pin "1") (pinfunction "1_1") (pintype "passive"))
      (node (ref "R13") (pin "1") (pinfunction "1_1") (pintype "passive"))
      (node (ref "R15") (pin "1") (pinfunction "1_1") (pintype "passive"))
      (node (ref "R18") (pin "2") (pinfunction "2_2") (pintype "passive"))
      (node (ref "R2") (pin "1") (pinfunction "1_1") (pintype "passive"))
      (node (ref "R29") (pin "1") (pinfunction "1_1") (pintype "passive"))
      (node (ref "R3") (pin "2") (pinfunction "2_2") (pintype "passive"))
      (node (ref "R7") (pin "1") (pinfunction "1_1") (pintype "passive"))
      (node (ref "R8") (pin "1") (pinfunction "1_1") (pintype "passive"))
      (node (ref "R9") (pin "1") (pinfunction "1_1") (pintype "passive"))
      (node (ref "S1") (pin "1") (pinfunction "S_1") (pintype "passive"))
      (node (ref "S1") (pin "2") (pinfunction "S1_2") (pintype "passive"))
      (node (ref "U1") (pin "12") (pinfunction "VSSA_12") (pintype "power_in"))
      (node (ref "U1") (pin "18") (pinfunction "VSS_18") (pintype "power_in"))
      (node (ref "U1") (pin "63") (pinfunction "VSS_63") (pintype "power_in"))
      (node (ref "U2") (pin "12") (pinfunction "SNA_12") (pintype "input"))
      (node (ref "U2") (pin "13") (pinfunction "SNB_13") (pintype "input"))
      (node (ref "U2") (pin "2") (pinfunction "PGND_2") (pintype "power_in"))
      (node (ref "U2") (pin "22") (pinfunction "SNC_22") (pintype "input"))
      (node (ref "U2") (pin "27") (pinfunction "DGND_27") (pintype "power_in"))
      (node (ref "U2") (pin "35") (pinfunction "AGND_35") (pintype "power_in"))
      (node (ref "U2") (pin "43") (pinfunction "BGND_43") (pintype "power_in"))
      (node (ref "U2") (pin "49") (pinfunction "EP_49") (pintype "power_in"))
      (node (ref "X1") (pin "2") (pinfunction "KL_2") (pintype "passive"))
    )
    (net (code "33") (name "GPIO_1") (class "Default")
      (node (ref "JP15") (pin "2") (pinfunction "2_2") (pintype "passive"))
      (node (ref "U1") (pin "8") (pinfunction "PC0_8") (pintype "bidirectional"))
    )
    (net (code "34") (name "GPIO_2") (class "Default")
      (node (ref "JP15") (pin "3") (pinfunction "3_3") (pintype "passive"))
      (node (ref "U1") (pin "9") (pinfunction "PC1_9") (pintype "bidirectional"))
    )
    (net (code "35") (name "GPIO_3") (class "Default")
      (node (ref "JP15") (pin "4") (pinfunction "4_4") (pintype "passive"))
      (node (ref "U1") (pin "10") (pinfunction "PC2/SPI2_MISO_10") (pintype "bidirectional"))
    )
    (net (code "36") (name "GPIO_4") (class "Default")
      (node (ref "JP15") (pin "5") (pinfunction "5_5") (pintype "passive"))
      (node (ref "U1") (pin "11") (pinfunction "PC3/SPI2_MOSI_11") (pintype "bidirectional"))
    )
    (net (code "37") (name "GPIO_5") (class "Default")
      (node (ref "JP15") (pin "6") (pinfunction "6_6") (pintype "passive"))
      (node (ref "U1") (pin "14") (pinfunction "PA0/WKUP_14") (pintype "bidirectional"))
    )
    (net (code "38") (name "GPIO_6") (class "Default")
      (node (ref "JP15") (pin "7") (pinfunction "7_7") (pintype "passive"))
      (node (ref "U1") (pin "15") (pinfunction "PA1/USART2_RTS_15") (pintype "bidirectional"))
    )
    (net (code "39") (name "INHA") (class "Default")
      (node (ref "JP4") (pin "7") (pinfunction "7_7") (pintype "passive"))
      (node (ref "R27") (pin "1") (pinfunction "1_1") (pintype "passive"))
      (node (ref "U2") (pin "37") (pinfunction "INHA_37") (pintype "input"))
    )
    (net (code "40") (name "INHB") (class "Default")
      (node (ref "JP4") (pin "5") (pinfunction "5_5") (pintype "passive"))
      (node (ref "R25") (pin "1") (pinfunction "1_1") (pintype "passive"))
      (node (ref "U2") (pin "39") (pinfunction "INHB_39") (pintype "input"))
    )
    (net (code "41") (name "INHC") (class "Default")
      (node (ref "JP4") (pin "3") (pinfunction "3_3") (pintype "passive"))
      (node (ref "R23") (pin "1") (pinfunction "1_1") (pintype "passive"))
      (node (ref "U2") (pin "41") (pinfunction "INHC_41") (pintype "input"))
    )
    (net (code "42") (name "INLA") (class "Default")
      (node (ref "JP4") (pin "6") (pinfunction "6_6") (pintype "passive"))
      (node (ref "R26") (pin "1") (pinfunction "1_1") (pintype "passive"))
      (node (ref "U2") (pin "38") (pinfunction "INLA_38") (pintype "input"))
    )
    (net (code "43") (name "INLB") (class "Default")
      (node (ref "JP4") (pin "4") (pinfunction "4_4") (pintype "passive"))
      (node (ref "R24") (pin "1") (pinfunction "1_1") (pintype "passive"))
      (node (ref "U2") (pin "40") (pinfunction "INLB_40") (pintype "input"))
    )
    (net (code "44") (name "INLC") (class "Default")
      (node (ref "JP4") (pin "2") (pinfunction "2_2") (pintype "passive"))
      (node (ref "R20") (pin "1") (pinfunction "1_1") (pintype "passive"))
      (node (ref "U2") (pin "42") (pinfunction "INLC_42") (pintype "input"))
    )
    (net (code "45") (name "LED") (class "Default")
      (node (ref "D4") (pin "A") (pinfunction "A_A") (pintype "passive"))
      (node (ref "U1") (pin "2") (pinfunction "PC13/RTC_OUT_2") (pintype "bidirectional"))
    )
    (net (code "46") (name "MISO") (class "Default")
      (node (ref "JP13") (pin "4") (pinfunction "4_4") (pintype "passive"))
      (node (ref "R21") (pin "2") (pinfunction "2_2") (pintype "passive"))
      (node (ref "U1") (pin "52") (pinfunction "PC11_52") (pintype "bidirectional"))
    )
    (net (code "47") (name "MOSI") (class "Default")
      (node (ref "JP13") (pin "3") (pinfunction "3_3") (pintype "passive"))
      (node (ref "R22") (pin "2") (pinfunction "2_2") (pintype "passive"))
      (node (ref "U1") (pin "53") (pinfunction "PC12_53") (pintype "bidirectional"))
    )
    (net (code "48") (name "NRST") (class "Default")
      (node (ref "C12") (pin "1") (pinfunction "1_1") (pintype "passive"))
      (node (ref "JP16") (pin "4") (pinfunction "4_4") (pintype "passive"))
      (node (ref "R30") (pin "1") (pinfunction "1_1") (pintype "passive"))
      (node (ref "S1") (pin "3") (pinfunction "P_3") (pintype "passive"))
      (node (ref "S1") (pin "4") (pinfunction "P1_4") (pintype "passive"))
      (node (ref "U1") (pin "7") (pinfunction "NRST_7") (pintype "bidirectional"))
    )
    (net (code "49") (name "Net-(D2-PadC)") (class "Default")
      (node (ref "D2") (pin "C") (pinfunction "C_C") (pintype "passive"))
      (node (ref "R3") (pin "1") (pinfunction "1_1") (pintype "passive"))
    )
    (net (code "50") (name "Net-(D3-PadC)") (class "Default")
      (node (ref "D3") (pin "C") (pinfunction "C_C") (pintype "passive"))
      (node (ref "R6") (pin "2") (pinfunction "2_2") (pintype "passive"))
    )
    (net (code "51") (name "Net-(D4-PadC)") (class "Default")
      (node (ref "D4") (pin "C") (pinfunction "C_C") (pintype "passive"))
      (node (ref "R18") (pin "1") (pinfunction "1_1") (pintype "passive"))
    )
    (net (code "52") (name "Net-(R1-Pad1)") (class "Default")
      (node (ref "R1") (pin "1") (pinfunction "1_1") (pintype "passive"))
      (node (ref "R28") (pin "1") (pinfunction "1_1") (pintype "passive"))
      (node (ref "R29") (pin "2") (pinfunction "2_2") (pintype "passive"))
    )
    (net (code "53") (name "OSC_N") (class "Default")
      (node (ref "C7") (pin "2") (pinfunction "2_2") (pintype "passive"))
      (node (ref "Q1") (pin "2") (pinfunction "2_2") (pintype "passive"))
      (node (ref "U1") (pin "6") (pinfunction "PH1/OSC_OUT_6") (pintype "bidirectional"))
    )
    (net (code "54") (name "OSC_P") (class "Default")
      (node (ref "C6") (pin "2") (pinfunction "2_2") (pintype "passive"))
      (node (ref "Q1") (pin "1") (pinfunction "1_1") (pintype "passive"))
      (node (ref "U1") (pin "5") (pinfunction "PH0/OSC_IN_5") (pintype "bidirectional"))
    )
    (net (code "55") (name "SCL") (class "Default")
      (node (ref "JP12") (pin "2") (pinfunction "2_2") (pintype "passive"))
      (node (ref "R16") (pin "1") (pinfunction "1_1") (pintype "passive"))
      (node (ref "U1") (pin "29") (pinfunction "PB10_29") (pintype "bidirectional"))
    )
    (net (code "56") (name "SCLK") (class "Default")
      (node (ref "JP13") (pin "5") (pinfunction "5_5") (pintype "passive"))
      (node (ref "JP3") (pin "5") (pinfunction "5_5") (pintype "passive"))
      (node (ref "U1") (pin "51") (pinfunction "PC10_51") (pintype "bidirectional"))
      (node (ref "U2") (pin "31") (pinfunction "SCLK_31") (pintype "input"))
    )
    (net (code "57") (name "SCS") (class "Default")
      (node (ref "JP3") (pin "6") (pinfunction "6_6") (pintype "passive"))
      (node (ref "R19") (pin "1") (pinfunction "1_1") (pintype "passive"))
      (node (ref "U2") (pin "32") (pinfunction "SCS_N_32") (pintype "input"))
    )
    (net (code "58") (name "SDA") (class "Default")
      (node (ref "JP12") (pin "3") (pinfunction "3_3") (pintype "passive"))
      (node (ref "R17") (pin "1") (pinfunction "1_1") (pintype "passive"))
      (node (ref "U1") (pin "30") (pinfunction "PB11_30") (pintype "bidirectional"))
    )
    (net (code "59") (name "SDI") (class "Default")
      (node (ref "JP3") (pin "4") (pinfunction "4_4") (pintype "passive"))
      (node (ref "R22") (pin "1") (pinfunction "1_1") (pintype "passive"))
      (node (ref "U2") (pin "30") (pinfunction "SDI_30") (pintype "input"))
    )
    (net (code "60") (name "SDO") (class "Default")
      (node (ref "JP3") (pin "3") (pinfunction "3_3") (pintype "passive"))
      (node (ref "R21") (pin "1") (pinfunction "1_1") (pintype "passive"))
      (node (ref "R4") (pin "1") (pinfunction "1_1") (pintype "passive"))
      (node (ref "U2") (pin "29") (pinfunction "SDO_29") (pintype "output"))
    )
    (net (code "61") (name "SHA") (class "Default")
      (node (ref "Q2") (pin "1") (pinfunction "S_1") (pintype "bidirectional"))
      (node (ref "Q2") (pin "2") (pinfunction "S_2") (pintype "bidirectional"))
      (node (ref "Q2") (pin "3") (pinfunction "S_3") (pintype "bidirectional"))
      (node (ref "Q3") (pin "5") (pinfunction "D_5") (pintype "bidirectional"))
      (node (ref "Q3") (pin "6") (pinfunction "D_6") (pintype "bidirectional"))
      (node (ref "Q3") (pin "7") (pinfunction "D_7") (pintype "bidirectional"))
      (node (ref "Q3") (pin "8") (pinfunction "D_8") (pintype "bidirectional"))
      (node (ref "Q3") (pin "9") (pinfunction "D_9") (pintype "bidirectional"))
      (node (ref "R10") (pin "2") (pinfunction "2_2") (pintype "passive"))
      (node (ref "U2") (pin "9") (pinfunction "SHA_9") (pintype "input"))
      (node (ref "X2") (pin "3") (pinfunction "KL_3") (pintype "passive"))
    )
    (net (code "62") (name "SHB") (class "Default")
      (node (ref "Q4") (pin "1") (pinfunction "S_1") (pintype "bidirectional"))
      (node (ref "Q4") (pin "2") (pinfunction "S_2") (pintype "bidirectional"))
      (node (ref "Q4") (pin "3") (pinfunction "S_3") (pintype "bidirectional"))
      (node (ref "Q5") (pin "5") (pinfunction "D_5") (pintype "bidirectional"))
      (node (ref "Q5") (pin "6") (pinfunction "D_6") (pintype "bidirectional"))
      (node (ref "Q5") (pin "7") (pinfunction "D_7") (pintype "bidirectional"))
      (node (ref "Q5") (pin "8") (pinfunction "D_8") (pintype "bidirectional"))
      (node (ref "Q5") (pin "9") (pinfunction "D_9") (pintype "bidirectional"))
      (node (ref "R12") (pin "2") (pinfunction "2_2") (pintype "passive"))
      (node (ref "U2") (pin "16") (pinfunction "SHB_16") (pintype "input"))
      (node (ref "X2") (pin "2") (pinfunction "KL_2") (pintype "passive"))
    )
    (net (code "63") (name "SHC") (class "Default")
      (node (ref "Q6") (pin "1") (pinfunction "S_1") (pintype "bidirectional"))
      (node (ref "Q6") (pin "2") (pinfunction "S_2") (pintype "bidirectional"))
      (node (ref "Q6") (pin "3") (pinfunction "S_3") (pintype "bidirectional"))
      (node (ref "Q7") (pin "5") (pinfunction "D_5") (pintype "bidirectional"))
      (node (ref "Q7") (pin "6") (pinfunction "D_6") (pintype "bidirectional"))
      (node (ref "Q7") (pin "7") (pinfunction "D_7") (pintype "bidirectional"))
      (node (ref "Q7") (pin "8") (pinfunction "D_8") (pintype "bidirectional"))
      (node (ref "Q7") (pin "9") (pinfunction "D_9") (pintype "bidirectional"))
      (node (ref "R14") (pin "2") (pinfunction "2_2") (pintype "passive"))
      (node (ref "U2") (pin "19") (pinfunction "SHC_19") (pintype "input"))
      (node (ref "X2") (pin "1") (pinfunction "KL_1") (pintype "passive"))
    )
    (net (code "64") (name "SOA") (class "Default")
      (node (ref "C23") (pin "1") (pinfunction "1_1") (pintype "passive"))
      (node (ref "JP5") (pin "4") (pinfunction "4_4") (pintype "passive"))
      (node (ref "U2") (pin "25") (pinfunction "SOA_25") (pintype "output"))
    )
    (net (code "65") (name "SOB") (class "Default")
      (node (ref "C24") (pin "1") (pinfunction "1_1") (pintype "passive"))
      (node (ref "JP5") (pin "3") (pinfunction "3_3") (pintype "passive"))
      (node (ref "U2") (pin "24") (pinfunction "SOB_24") (pintype "output"))
    )
    (net (code "66") (name "SOC") (class "Default")
      (node (ref "C25") (pin "1") (pinfunction "1_1") (pintype "passive"))
      (node (ref "JP5") (pin "2") (pinfunction "2_2") (pintype "passive"))
      (node (ref "U2") (pin "23") (pinfunction "SOC_23") (pintype "output"))
    )
    (net (code "67") (name "SPA") (class "Default")
      (node (ref "C29") (pin "1") (pinfunction "1_1") (pintype "passive"))
      (node (ref "Q3") (pin "1") (pinfunction "S_1") (pintype "bidirectional"))
      (node (ref "Q3") (pin "2") (pinfunction "S_2") (pintype "bidirectional"))
      (node (ref "Q3") (pin "3") (pinfunction "S_3") (pintype "bidirectional"))
      (node (ref "R7") (pin "2") (pinfunction "2_2") (pintype "passive"))
      (node (ref "U2") (pin "11") (pinfunction "SPA_11") (pintype "input"))
    )
    (net (code "68") (name "SPB") (class "Default")
      (node (ref "C30") (pin "1") (pinfunction "1_1") (pintype "passive"))
      (node (ref "Q5") (pin "1") (pinfunction "S_1") (pintype "bidirectional"))
      (node (ref "Q5") (pin "2") (pinfunction "S_2") (pintype "bidirectional"))
      (node (ref "Q5") (pin "3") (pinfunction "S_3") (pintype "bidirectional"))
      (node (ref "R8") (pin "2") (pinfunction "2_2") (pintype "passive"))
      (node (ref "U2") (pin "14") (pinfunction "SPB_14") (pintype "input"))
    )
    (net (code "69") (name "SPC") (class "Default")
      (node (ref "C31") (pin "1") (pinfunction "1_1") (pintype "passive"))
      (node (ref "Q7") (pin "1") (pinfunction "S_1") (pintype "bidirectional"))
      (node (ref "Q7") (pin "2") (pinfunction "S_2") (pintype "bidirectional"))
      (node (ref "Q7") (pin "3") (pinfunction "S_3") (pintype "bidirectional"))
      (node (ref "R9") (pin "2") (pinfunction "2_2") (pintype "passive"))
      (node (ref "U2") (pin "21") (pinfunction "SPC_21") (pintype "input"))
    )
    (net (code "70") (name "SWCLK") (class "Default")
      (node (ref "JP16") (pin "2") (pinfunction "2_2") (pintype "passive"))
      (node (ref "U1") (pin "49") (pinfunction "PA14/JTCK-SWCLK_49") (pintype "bidirectional"))
    )
    (net (code "71") (name "SWDIO") (class "Default")
      (node (ref "JP16") (pin "1") (pinfunction "1_1") (pintype "passive"))
      (node (ref "U1") (pin "46") (pinfunction "PA13/JMS-SWDIO_46") (pintype "bidirectional"))
    )
    (net (code "72") (name "VCAP_1") (class "Default")
      (node (ref "C9") (pin "1") (pinfunction "1_1") (pintype "passive"))
      (node (ref "U1") (pin "31") (pinfunction "VCAP_1_31") (pintype "power_in"))
    )
    (net (code "73") (name "VCAP_2") (class "Default")
      (node (ref "C8") (pin "1") (pinfunction "1_1") (pintype "passive"))
      (node (ref "U1") (pin "47") (pinfunction "VCAP_2_47") (pintype "power_in"))
    )
    (net (code "74") (name "VCP") (class "Default")
      (node (ref "C19") (pin "2") (pinfunction "2_2") (pintype "passive"))
      (node (ref "U2") (pin "5") (pinfunction "VCP_5") (pintype "power_in"))
    )
    (net (code "75") (name "VIN") (class "Default")
      (node (ref "U2") (pin "47") (pinfunction "VIN_47") (pintype "power_in"))
    )
    (net (code "76") (name "VSENA") (class "Default")
      (node (ref "JP6") (pin "1") (pinfunction "1_1") (pintype "passive"))
      (node (ref "R10") (pin "1") (pinfunction "1_1") (pintype "passive"))
      (node (ref "R11") (pin "2") (pinfunction "2_2") (pintype "passive"))
    )
    (net (code "77") (name "VSENB") (class "Default")
      (node (ref "JP6") (pin "2") (pinfunction "2_2") (pintype "passive"))
      (node (ref "R12") (pin "1") (pinfunction "1_1") (pintype "passive"))
      (node (ref "R13") (pin "2") (pinfunction "2_2") (pintype "passive"))
    )
    (net (code "78") (name "VSENC") (class "Default")
      (node (ref "JP6") (pin "3") (pinfunction "3_3") (pintype "passive"))
      (node (ref "R14") (pin "1") (pinfunction "1_1") (pintype "passive"))
      (node (ref "R15") (pin "2") (pinfunction "2_2") (pintype "passive"))
    )
    (net (code "79") (name "unconnected-(U1-PA2{slash}USART2_TX-Pad16)") (class "Default")
      (node (ref "U1") (pin "16") (pinfunction "PA2/USART2_TX_16") (pintype "bidirectional"))
    )
    (net (code "80") (name "unconnected-(U1-PA3{slash}USART2_RX-Pad17)") (class "Default")
      (node (ref "U1") (pin "17") (pinfunction "PA3/USART2_RX_17") (pintype "bidirectional"))
    )
    (net (code "81") (name "unconnected-(U1-PA4{slash}USART2_CK-Pad20)") (class "Default")
      (node (ref "U1") (pin "20") (pinfunction "PA4/USART2_CK_20") (pintype "bidirectional"))
    )
    (net (code "82") (name "unconnected-(U1-PA5{slash}SPI1_SCK-Pad21)") (class "Default")
      (node (ref "U1") (pin "21") (pinfunction "PA5/SPI1_SCK_21") (pintype "bidirectional"))
    )
    (net (code "83") (name "unconnected-(U1-PA8-Pad41)") (class "Default")
      (node (ref "U1") (pin "41") (pinfunction "PA8_41") (pintype "bidirectional"))
    )
    (net (code "84") (name "unconnected-(U1-PA12-Pad45)") (class "Default")
      (node (ref "U1") (pin "45") (pinfunction "PA12_45") (pintype "bidirectional"))
    )
    (net (code "85") (name "unconnected-(U1-PA15-Pad50)") (class "Default")
      (node (ref "U1") (pin "50") (pinfunction "PA15_50") (pintype "bidirectional"))
    )
    (net (code "86") (name "unconnected-(U1-PB3-Pad55)") (class "Default")
      (node (ref "U1") (pin "55") (pinfunction "PB3_55") (pintype "bidirectional"))
    )
    (net (code "87") (name "unconnected-(U1-PB4-Pad56)") (class "Default")
      (node (ref "U1") (pin "56") (pinfunction "PB4_56") (pintype "bidirectional"))
    )
    (net (code "88") (name "unconnected-(U1-PB6-Pad58)") (class "Default")
      (node (ref "U1") (pin "58") (pinfunction "PB6_58") (pintype "bidirectional"))
    )
    (net (code "89") (name "unconnected-(U1-PB7-Pad59)") (class "Default")
      (node (ref "U1") (pin "59") (pinfunction "PB7_59") (pintype "bidirectional"))
    )
    (net (code "90") (name "unconnected-(U1-PB8-Pad61)") (class "Default")
      (node (ref "U1") (pin "61") (pinfunction "PB8_61") (pintype "bidirectional"))
    )
    (net (code "91") (name "unconnected-(U1-PB9-Pad62)") (class "Default")
      (node (ref "U1") (pin "62") (pinfunction "PB9_62") (pintype "bidirectional"))
    )
    (net (code "92") (name "unconnected-(U1-PB12-Pad33)") (class "Default")
      (node (ref "U1") (pin "33") (pinfunction "PB12_33") (pintype "bidirectional"))
    )
    (net (code "93") (name "unconnected-(U1-PB13-Pad34)") (class "Default")
      (node (ref "U1") (pin "34") (pinfunction "PB13_34") (pintype "bidirectional"))
    )
    (net (code "94") (name "unconnected-(U1-PB14-Pad35)") (class "Default")
      (node (ref "U1") (pin "35") (pinfunction "PB14_35") (pintype "bidirectional"))
    )
    (net (code "95") (name "unconnected-(U1-PB15-Pad36)") (class "Default")
      (node (ref "U1") (pin "36") (pinfunction "PB15_36") (pintype "bidirectional"))
    )
    (net (code "96") (name "unconnected-(U1-PC9-Pad40)") (class "Default")
      (node (ref "U1") (pin "40") (pinfunction "PC9_40") (pintype "bidirectional"))
    )
    (net (code "97") (name "unconnected-(U1-PC14{slash}OSC32_IN-Pad3)") (class "Default")
      (node (ref "U1") (pin "3") (pinfunction "PC14/OSC32_IN_3") (pintype "bidirectional"))
    )
    (net (code "98") (name "unconnected-(U1-PC15{slash}OSC32_OUT-Pad4)") (class "Default")
      (node (ref "U1") (pin "4") (pinfunction "PC15/OSC32_OUT_4") (pintype "bidirectional"))
    )
    (net (code "99") (name "unconnected-(U1-PD2-Pad54)") (class "Default")
      (node (ref "U1") (pin "54") (pinfunction "PD2_54") (pintype "bidirectional"))
    )
    (net (code "100") (name "unconnected-(U2-FB-Pad1)") (class "Default")
      (node (ref "U2") (pin "1") (pinfunction "FB_1") (pintype "input"))
    )
    (net (code "101") (name "unconnected-(U2-NC-Pad46)") (class "Default")
      (node (ref "U2") (pin "46") (pinfunction "NC_46") (pintype "no_connect"))
    )
    (net (code "102") (name "unconnected-(U2-SHDN_N-Pad48)") (class "Default")
      (node (ref "U2") (pin "48") (pinfunction "SHDN_N_48") (pintype "input"))
    )
    (net (code "103") (name "unconnected-(U2-SW-Pad45)") (class "Default")
      (node (ref "U2") (pin "45") (pinfunction "SW_45") (pintype "output"))
    )
  )
)
